# PowerV1_2.net
KiCad netlist of a schematic drawn in Altium Designer
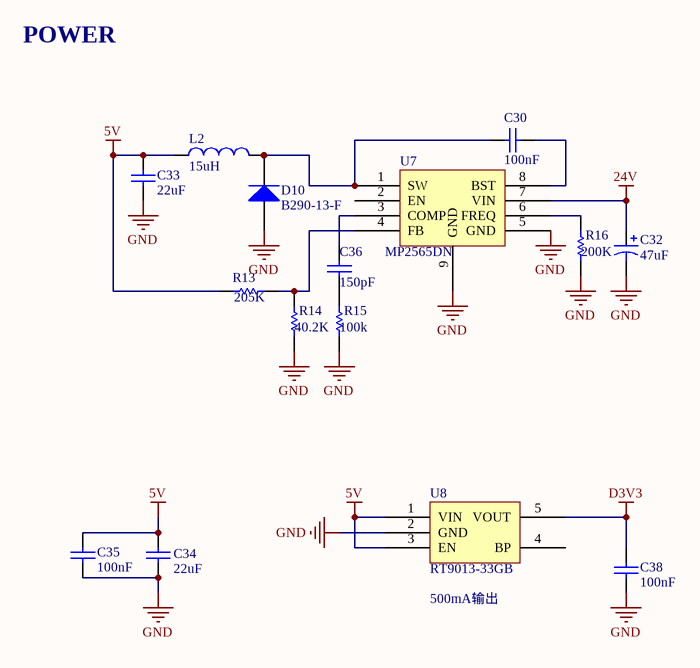
[diagram p0: PowerV1.2.SchDoc]

(export (version "E")
  (design (tool "Eeschema 10.0.6"))
  (components
    (comp (ref "C30")
      (value "100nF")
      (footprint "BinFeng:0402")
      (description "Capacitor")
      (fields (field (name "PUBLISHER") "Altium Limited"))
      (libsource (lib "Miscellaneous Devices") (part "Cap"))
    )
    (comp (ref "C32")
      (value "47uF")
      (footprint "cap_pol_8*10.2")
      (description "Polarized Capacitor (Radial)")
      (fields (field (name "PUBLISHER") "Altium Limited"))
      (libsource (lib "Miscellaneous Devices") (part "Cap Pol1"))
    )
    (comp (ref "C33")
      (value "22uF")
      (footprint "0805")
      (description "Capacitor,50V")
      (fields (field (name "PUBLISHER") "Altium Limited"))
      (libsource (lib "Miscellaneous Devices") (part "Cap"))
    )
    (comp (ref "C34")
      (value "22uF")
      (footprint "1206")
      (description "Capacitor")
      (fields (field (name "PUBLISHER") "Altium Limited"))
      (libsource (lib "Miscellaneous Devices") (part "Cap"))
    )
    (comp (ref "C35")
      (value "100nF")
      (footprint "BinFeng:0402")
      (description "Capacitor,100V")
      (fields (field (name "PUBLISHER") "Altium Limited"))
      (libsource (lib "Miscellaneous Devices") (part "Cap"))
    )
    (comp (ref "C36")
      (value "150pF")
      (footprint "BinFeng:0402")
      (description "Capacitor")
      (fields (field (name "PUBLISHER") "Altium Limited"))
      (libsource (lib "Miscellaneous Devices") (part "Cap"))
    )
    (comp (ref "C38")
      (value "100nF")
      (footprint "BinFeng:0402")
      (description "Capacitor 3V3")
      (fields (field (name "PUBLISHER") "Altium Limited"))
      (libsource (lib "Miscellaneous Devices") (part "Cap"))
    )
    (comp (ref "D10")
      (value "B290-13-F")
      (footprint "B290")
      (description "Default Diode")
      (fields (field (name "PUBLISHER") "Altium Limited"))
      (libsource (lib "Miscellaneous Devices") (part "Diode"))
    )
    (comp (ref "L2")
      (value "15uH")
      (footprint "10*10Inductor")
      (description "Inductor, 1A")
      (fields (field (name "PUBLISHER") "Altium Limited"))
      (libsource (lib "Miscellaneous Devices") (part "Inductor"))
    )
    (comp (ref "R13")
      (value "205K")
      (footprint "BinFeng:0402")
      (description "Resistor")
      (fields (field (name "PUBLISHER") "Altium Limited"))
      (libsource (lib "Miscellaneous Devices") (part "Res1"))
    )
    (comp (ref "R14")
      (value "40.2K")
      (footprint "BinFeng:0402")
      (description "Resistor")
      (fields (field (name "PUBLISHER") "Altium Limited"))
      (libsource (lib "Miscellaneous Devices") (part "Res1"))
    )
    (comp (ref "R15")
      (value "100k")
      (footprint "BinFeng:0402")
      (description "Resistor")
      (fields (field (name "PUBLISHER") "Altium Limited"))
      (libsource (lib "Miscellaneous Devices") (part "Res1"))
    )
    (comp (ref "R16")
      (value "200K")
      (footprint "BinFeng:0402")
      (description "Resistor")
      (fields (field (name "PUBLISHER") "Altium Limited"))
      (libsource (lib "Miscellaneous Devices") (part "Res1"))
    )
    (comp (ref "U7") (value "MP2565DN") (footprint "MP2565DN") (libsource (lib "hg") (part "MP2565DN")))
    (comp (ref "U8")
      (value "RT9013-33GB")
      (footprint "SOT-23-5")
      (libsource (lib "BinFeng_IC") (part "RT9193"))
    )
  )
  (nets
    (net (code "1") (name "5V") (class "Default")
      (node (ref "C33") (pin "2") (pinfunction "2_2") (pintype "passive"))
      (node (ref "C34") (pin "2") (pinfunction "2_2") (pintype "passive"))
      (node (ref "C35") (pin "2") (pinfunction "2_2") (pintype "passive"))
      (node (ref "L2") (pin "1") (pinfunction "1_1") (pintype "passive"))
      (node (ref "R13") (pin "2") (pinfunction "2_2") (pintype "passive"))
      (node (ref "U8") (pin "1") (pinfunction "VIN_1") (pintype "passive"))
      (node (ref "U8") (pin "3") (pinfunction "EN_3") (pintype "passive"))
    )
    (net (code "2") (name "24V") (class "Default")
      (node (ref "C32") (pin "1") (pinfunction "1_1") (pintype "passive"))
      (node (ref "U7") (pin "7") (pinfunction "VIN_7") (pintype "passive"))
    )
    (net (code "3") (name "D3V3") (class "Default")
      (node (ref "C38") (pin "2") (pinfunction "2_2") (pintype "passive"))
      (node (ref "U8") (pin "5") (pinfunction "VOUT_5") (pintype "passive"))
    )
    (net (code "4") (name "GND") (class "Default")
      (node (ref "C32") (pin "2") (pinfunction "2_2") (pintype "passive"))
      (node (ref "C33") (pin "1") (pinfunction "1_1") (pintype "passive"))
      (node (ref "C34") (pin "1") (pinfunction "1_1") (pintype "passive"))
      (node (ref "C35") (pin "1") (pinfunction "1_1") (pintype "passive"))
      (node (ref "C38") (pin "1") (pinfunction "1_1") (pintype "passive"))
      (node (ref "D10") (pin "1") (pinfunction "A_1") (pintype "passive"))
      (node (ref "R14") (pin "1") (pinfunction "1_1") (pintype "passive"))
      (node (ref "R15") (pin "1") (pinfunction "1_1") (pintype "passive"))
      (node (ref "R16") (pin "1") (pinfunction "1_1") (pintype "passive"))
      (node (ref "U7") (pin "5") (pinfunction "GND_5") (pintype "passive"))
      (node (ref "U7") (pin "9") (pinfunction "GND_9") (pintype "passive"))
      (node (ref "U8") (pin "2") (pinfunction "GND_2") (pintype "passive"))
    )
    (net (code "5") (name "Net-(C36-Pad2)") (class "Default")
      (node (ref "C36") (pin "2") (pinfunction "2_2") (pintype "passive"))
      (node (ref "R15") (pin "2") (pinfunction "2_2") (pintype "passive"))
    )
    (net (code "6") (name "Net-(D10-K)") (class "Default")
      (node (ref "C30") (pin "2") (pinfunction "2_2") (pintype "passive"))
      (node (ref "D10") (pin "2") (pinfunction "K_2") (pintype "passive"))
      (node (ref "L2") (pin "2") (pinfunction "2_2") (pintype "passive"))
      (node (ref "U7") (pin "1") (pinfunction "SW_1") (pintype "passive"))
    )
    (net (code "7") (name "Net-(U7-BST)") (class "Default")
      (node (ref "C30") (pin "1") (pinfunction "1_1") (pintype "passive"))
      (node (ref "U7") (pin "8") (pinfunction "BST_8") (pintype "passive"))
    )
    (net (code "8") (name "Net-(U7-COMP)") (class "Default")
      (node (ref "C36") (pin "1") (pinfunction "1_1") (pintype "passive"))
      (node (ref "U7") (pin "3") (pinfunction "COMP_3") (pintype "passive"))
    )
    (net (code "9") (name "Net-(U7-FB)") (class "Default")
      (node (ref "R13") (pin "1") (pinfunction "1_1") (pintype "passive"))
      (node (ref "R14") (pin "2") (pinfunction "2_2") (pintype "passive"))
      (node (ref "U7") (pin "4") (pinfunction "FB_4") (pintype "passive"))
    )
    (net (code "10") (name "Net-(U7-FREQ)") (class "Default")
      (node (ref "R16") (pin "2") (pinfunction "2_2") (pintype "passive"))
      (node (ref "U7") (pin "6") (pinfunction "FREQ_6") (pintype "passive"))
    )
    (net (code "11") (name "unconnected-(U7-EN-Pad2)") (class "Default")
      (node (ref "U7") (pin "2") (pinfunction "EN_2") (pintype "passive"))
    )
    (net (code "12") (name "unconnected-(U8-BP-Pad4)") (class "Default")
      (node (ref "U8") (pin "4") (pinfunction "BP_4") (pintype "passive"))
    )
  )
)
